# USB_PC.net
KiCad netlist of a schematic drawn in Altium Designer
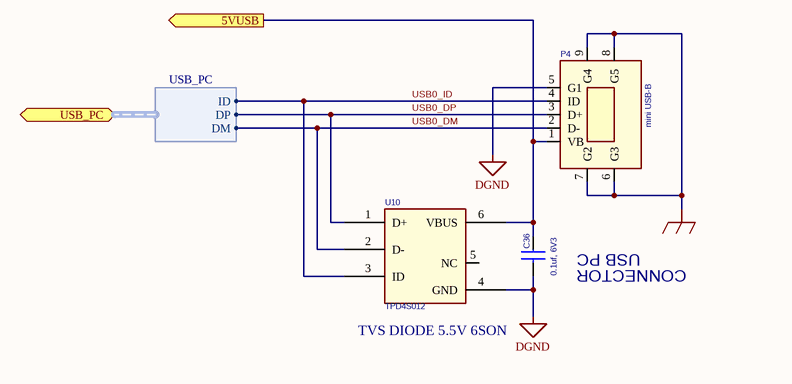
[diagram p0: USB_PC.SchDoc]

(export (version "E")
  (design (tool "Eeschema 10.0.6"))
  (components
    (comp (ref "C36")
      (value "0.1uf, 6V3")
      (footprint "402")
      (description "CAP CER 0.1UF 6.3V 10% X5R 0402")
      (fields
        (field (name "MANUFACTURER") "TDK Corporation")
        (field (name "MANUFACTURER PART NUMBER") "C1005X5R0J104K050BA")
      )
      (libsource (lib "BEAGLEBONEBLACK_REV A5B") (part "CAP_0.1uF_X7R_16V_10% 0402"))
    )
    (comp (ref "P4")
      (value "mini USB-B")
      (footprint "USB5MINI_4SHIELDED_SMD-5")
      (description "CONN RCPT USB MINI B R/A SMD")
      (fields (field (name "MANUFACTURER") "KYCON") (field (name "MANUFACTURER PART NUMBER") "0565790576"))
      (libsource (lib "BEAGLEBONEBLACK_REV A5B") (part "MINI-USB-AB-SOCKET"))
    )
    (comp (ref "U10")
      (value "TPD4S012")
      (footprint "U_6_DRY")
      (description "ESD 4channel USB Interface")
      (fields (field (name "MFR") "TI") (field (name "TIINTPARTNUMBER") "1A0233"))
      (libsource (lib "BEAGLEBONEBLACK_REV A5B") (part "PROT_TPD4S012"))
    )
  )
  (nets
    (net (code "2") (name "/5VUSB") (class "Default")
      (node (ref "C36") (pin "1") (pinfunction "1_1") (pintype "passive"))
      (node (ref "P4") (pin "1") (pinfunction "VB_1") (pintype "passive"))
      (node (ref "U10") (pin "6") (pinfunction "VBUS_6") (pintype "power_in"))
    )
    (net (code "3") (name "/USB0_DM") (class "Default")
      (node (ref "P4") (pin "2") (pinfunction "D-_2") (pintype "passive"))
      (node (ref "U10") (pin "2") (pinfunction "D-_2") (pintype "passive"))
    )
    (net (code "4") (name "/USB0_DP") (class "Default")
      (node (ref "P4") (pin "3") (pinfunction "D+_3") (pintype "passive"))
      (node (ref "U10") (pin "1") (pinfunction "D+_1") (pintype "passive"))
    )
    (net (code "5") (name "/USB0_ID") (class "Default")
      (node (ref "P4") (pin "4") (pinfunction "ID_4") (pintype "passive"))
      (node (ref "U10") (pin "3") (pinfunction "ID_3") (pintype "passive"))
    )
    (net (code "7") (name "DGND") (class "Default")
      (node (ref "C36") (pin "2") (pinfunction "2_2") (pintype "passive"))
      (node (ref "P4") (pin "5") (pinfunction "G1_5") (pintype "passive"))
      (node (ref "U10") (pin "4") (pinfunction "GND_4") (pintype "power_in"))
    )
    (net (code "8") (name "GND_EARTH") (class "Default")
      (node (ref "P4") (pin "6") (pinfunction "G3_6") (pintype "passive"))
      (node (ref "P4") (pin "7") (pinfunction "G2_7") (pintype "passive"))
      (node (ref "P4") (pin "8") (pinfunction "G5_8") (pintype "passive"))
      (node (ref "P4") (pin "9") (pinfunction "G4_9") (pintype "passive"))
    )
    (net (code "9") (name "unconnected-(U10-NC-Pad5)") (class "Default")
      (node (ref "U10") (pin "5") (pinfunction "NC_5") (pintype "passive"))
    )
  )
)
